# Liquid_Boost.net
KiCad netlist of a schematic drawn in Altium Designer
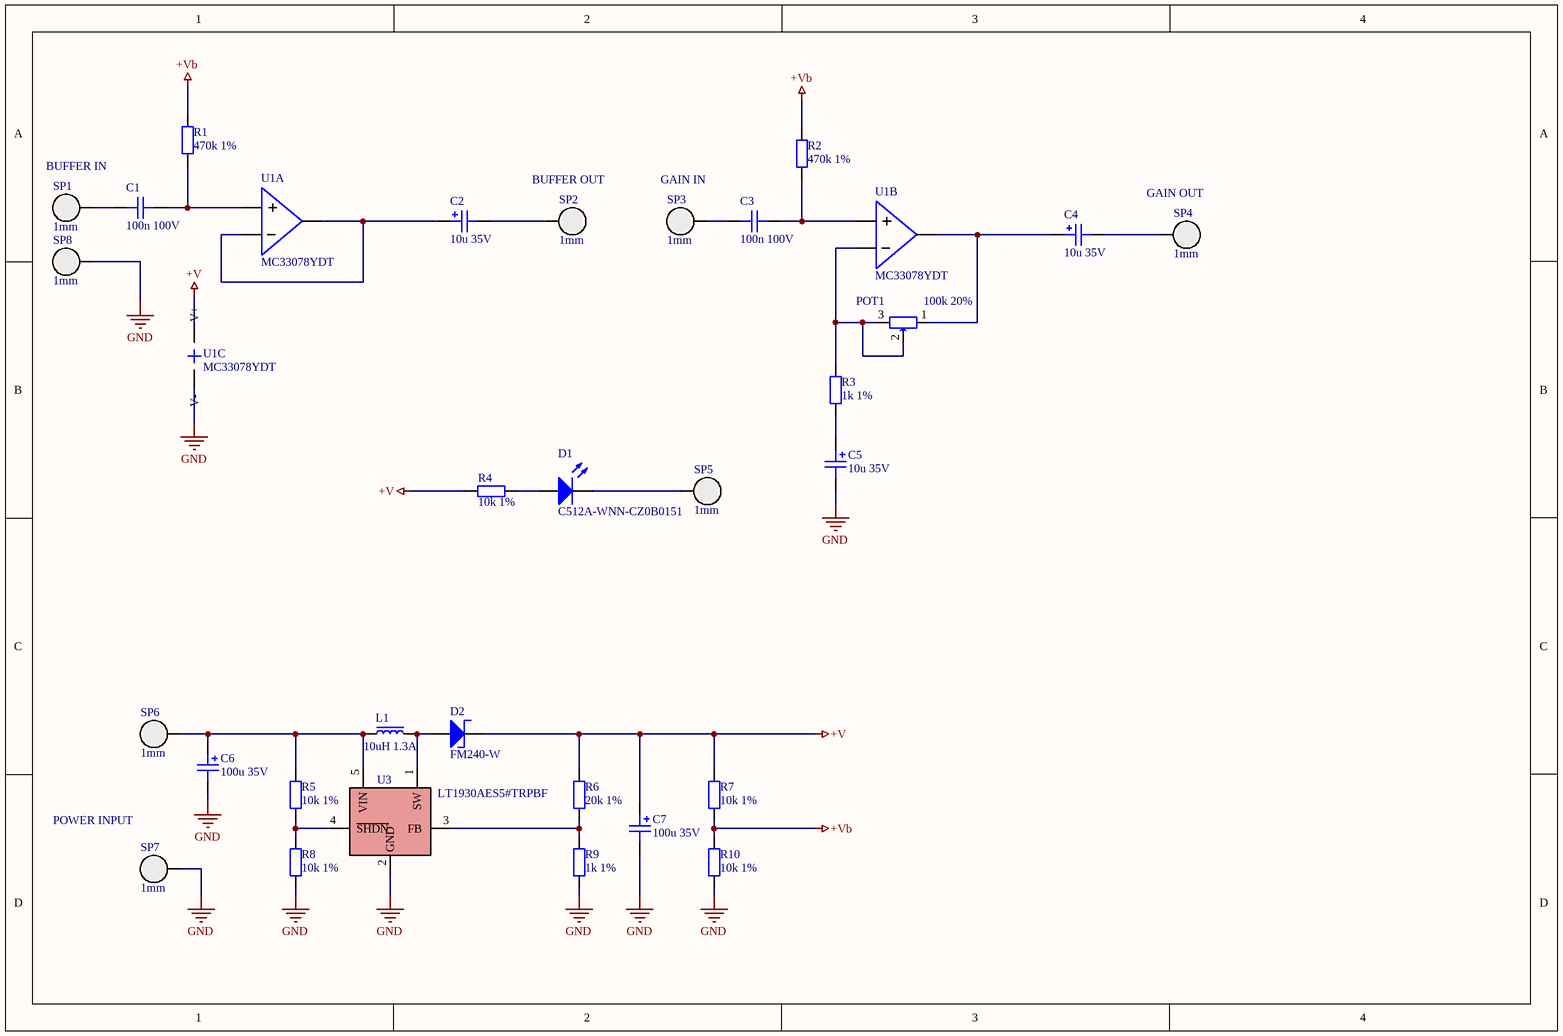
[diagram p0: Liquid Boost.SchDoc]

(export (version "E")
  (design (tool "Eeschema 10.0.6"))
  (components
    (comp (ref "C1")
      (value "100n 100V")
      (footprint "Liquid Boost:R82EC3100AA70K")
      (description "Film Capacitors 100V 0.1uF 10% LS=5mm AEC-Q200")
      (fields (field (name "MANUFACTURER PART NUMBER") "R82EC3100AA70K"))
      (libsource (lib "Liquid Boost") (part "Capacitor 100n 10% 100V R82EC3100AA70K"))
    )
    (comp (ref "C2")
      (value "10u 35V")
      (footprint "Liquid Boost:860010573007")
      (description "Aluminum Electrolytic Capacitors - Radial Leaded 10uF 35V 20% Audio SILMIC II")
      (fields (field (name "MANUFACTURER PART NUMBER") "RFS-35V100ME3#5"))
      (libsource (lib "Liquid Boost") (part "Capacitor 10u 35V 20% 5mm THT RFS-35V100ME3#5"))
    )
    (comp (ref "C3")
      (value "100n 100V")
      (footprint "Liquid Boost:R82EC3100AA70K")
      (description "Film Capacitors 100V 0.1uF 10% LS=5mm AEC-Q200")
      (fields (field (name "MANUFACTURER PART NUMBER") "R82EC3100AA70K"))
      (libsource (lib "Liquid Boost") (part "Capacitor 100n 10% 100V R82EC3100AA70K"))
    )
    (comp (ref "C4")
      (value "10u 35V")
      (footprint "Liquid Boost:860010573007")
      (description "Aluminum Electrolytic Capacitors - Radial Leaded 10uF 35V 20% Audio SILMIC II")
      (fields (field (name "MANUFACTURER PART NUMBER") "RFS-35V100ME3#5"))
      (libsource (lib "Liquid Boost") (part "Capacitor 10u 35V 20% 5mm THT RFS-35V100ME3#5"))
    )
    (comp (ref "C5")
      (value "10u 35V")
      (footprint "Liquid Boost:860010573007")
      (description "Aluminum Electrolytic Capacitors - Radial Leaded 10uF 35V 20% Audio SILMIC II")
      (fields (field (name "MANUFACTURER PART NUMBER") "RFS-35V100ME3#5"))
      (libsource (lib "Liquid Boost") (part "Capacitor 10u 35V 20% 5mm THT RFS-35V100ME3#5"))
    )
    (comp (ref "C6")
      (value "100u 35V")
      (footprint "Liquid Boost:860010573007")
      (description "Aluminum Electrolytic Capacitors - Radial Leaded WCAP-ATG8 100uF 35V 20% Radial")
      (fields (field (name "MANUFACTURER PART NUMBER") "860010573007"))
      (libsource (lib "Liquid Boost") (part "Capacitor 100u 35V 20% 6.3mm THT 860010573007"))
    )
    (comp (ref "C7")
      (value "100u 35V")
      (footprint "Liquid Boost:860010573007")
      (description "Aluminum Electrolytic Capacitors - Radial Leaded WCAP-ATG8 100uF 35V 20% Radial")
      (fields (field (name "MANUFACTURER PART NUMBER") "860010573007"))
      (libsource (lib "Liquid Boost") (part "Capacitor 100u 35V 20% 6.3mm THT 860010573007"))
    )
    (comp (ref "D1")
      (value "C512A-WNN-CZ0B0151")
      (footprint "Liquid Boost:C512A-WNN-CZ0B0151")
      (description "Standard LEDs - Through Hole Cool White 4600K 8200-23500mcd")
      (libsource (lib "Liquid Boost") (part "Diode LED 5mm White THT C512A-WNN-CZ0B0151"))
    )
    (comp (ref "D2")
      (value "FM240-W")
      (footprint "Liquid Boost:FM240-W")
      (description "Schottky Diodes & Rectifiers 2A 40V Schottky")
      (libsource (lib "Liquid Boost") (part "Diode Schottky 2A 40V FM240-W"))
    )
    (comp (ref "L1")
      (value "10uH 1.3A")
      (footprint "Liquid Boost:VLS252012HBX-100M-1")
      (description "Fixed Inductors 10uH 1.3A 540mOhms Power Circuits")
      (fields (field (name "MANUFACTURER PART NUMBER") "VLS252012HBX-100M-1"))
      (libsource (lib "Liquid Boost") (part "Inductor 10uH 1.3A 540mOhms VLS252012HBX-100M-1"))
    )
    (comp (ref "POT1")
      (value "100k 20%")
      (footprint "Liquid Boost:PTV09A")
      (description "Potentiometers 100K 20% 9MM CARBON POT")
      (fields (field (name "MANUFACTURER PART NUMBER") "PTV09A-4015F-B104"))
      (libsource (lib "Liquid Boost") (part "Potentiometer 100k 20% PTV09A-4015F-B104"))
    )
    (comp (ref "R1")
      (value "470k 1%")
      (footprint "Liquid Boost:Resistor 0603")
      (description "Thin Film Resistors - SMD 1/10W 470K ohm 1% 50ppm")
      (fields (field (name "MANUFACTURER PART NUMBER") "RT0603FRE07470KL"))
      (libsource (lib "Liquid Boost") (part "Resistor 470k 1% RT0603FRE07470KL"))
    )
    (comp (ref "R2")
      (value "470k 1%")
      (footprint "Liquid Boost:Resistor 0603")
      (description "Thin Film Resistors - SMD 1/10W 470K ohm 1% 50ppm")
      (fields (field (name "MANUFACTURER PART NUMBER") "RT0603FRE07470KL"))
      (libsource (lib "Liquid Boost") (part "Resistor 470k 1% RT0603FRE07470KL"))
    )
    (comp (ref "R3")
      (value "1k 1%")
      (footprint "Liquid Boost:Resistor 0603")
      (description "Thin Film Resistors - SMD 1K ohm 1% 1/10W")
      (fields (field (name "MANUFACTURER PART NUMBER") "RT0603FRE071KL"))
      (libsource (lib "Liquid Boost") (part "Resistor 1k 1% RT0603FRE071KL"))
    )
    (comp (ref "R4")
      (value "10k 1%")
      (footprint "Liquid Boost:Resistor 0603")
      (description "Thin Film Resistors - SMD 1/10W 10K ohm 1% 50ppm")
      (fields (field (name "MANUFACTURER PART NUMBER") "RT0603FRE0710KL"))
      (libsource (lib "") (part "Resistor 10k 1% RT0603FRE0710KL_1"))
    )
    (comp (ref "R5")
      (value "10k 1%")
      (footprint "Liquid Boost:Resistor 0603")
      (description "Thin Film Resistors - SMD 1/10W 10K ohm 1% 50ppm")
      (fields (field (name "MANUFACTURER PART NUMBER") "RT0603FRE0710KL"))
      (libsource (lib "Liquid Boost") (part "Resistor 10k 1% RT0603FRE0710KL"))
    )
    (comp (ref "R6")
      (value "20k 1%")
      (footprint "Liquid Boost:Resistor 0603")
      (description "Thin Film Resistors - SMD 1/10W 20K ohm 1% 50ppm")
      (fields (field (name "MANUFACTURER PART NUMBER") "RT0603FRE0720KL"))
      (libsource (lib "Liquid Boost") (part "Resistor 20k 1% RT0603FRE0720KL"))
    )
    (comp (ref "R7")
      (value "10k 1%")
      (footprint "Liquid Boost:Resistor 0603")
      (description "Thin Film Resistors - SMD 1/10W 10K ohm 1% 50ppm")
      (fields (field (name "MANUFACTURER PART NUMBER") "RT0603FRE0710KL"))
      (libsource (lib "Liquid Boost") (part "Resistor 10k 1% RT0603FRE0710KL"))
    )
    (comp (ref "R8")
      (value "10k 1%")
      (footprint "Liquid Boost:Resistor 0603")
      (description "Thin Film Resistors - SMD 1/10W 10K ohm 1% 50ppm")
      (fields (field (name "MANUFACTURER PART NUMBER") "RT0603FRE0710KL"))
      (libsource (lib "Liquid Boost") (part "Resistor 10k 1% RT0603FRE0710KL"))
    )
    (comp (ref "R9")
      (value "1k 1%")
      (footprint "Liquid Boost:Resistor 0603")
      (description "Thin Film Resistors - SMD 1K ohm 1% 1/10W")
      (fields (field (name "MANUFACTURER PART NUMBER") "RT0603FRE071KL"))
      (libsource (lib "Liquid Boost") (part "Resistor 1k 1% RT0603FRE071KL"))
    )
    (comp (ref "R10")
      (value "10k 1%")
      (footprint "Liquid Boost:Resistor 0603")
      (description "Thin Film Resistors - SMD 1/10W 10K ohm 1% 50ppm")
      (fields (field (name "MANUFACTURER PART NUMBER") "RT0603FRE0710KL"))
      (libsource (lib "Liquid Boost") (part "Resistor 10k 1% RT0603FRE0710KL"))
    )
    (comp (ref "SP1")
      (value "1mm")
      (footprint "Liquid Boost:SOLDER PAD 1mm")
      (libsource (lib "Liquid Boost") (part "Solder Pad 1mm"))
    )
    (comp (ref "SP2")
      (value "1mm")
      (footprint "Liquid Boost:SOLDER PAD 1mm")
      (libsource (lib "Liquid Boost") (part "Solder Pad 1mm"))
    )
    (comp (ref "SP3")
      (value "1mm")
      (footprint "Liquid Boost:SOLDER PAD 1mm")
      (libsource (lib "Liquid Boost") (part "Solder Pad 1mm"))
    )
    (comp (ref "SP4")
      (value "1mm")
      (footprint "Liquid Boost:SOLDER PAD 1mm")
      (libsource (lib "Liquid Boost") (part "Solder Pad 1mm"))
    )
    (comp (ref "SP5")
      (value "1mm")
      (footprint "Liquid Boost:SOLDER PAD 1mm")
      (libsource (lib "Liquid Boost") (part "Solder Pad 1mm"))
    )
    (comp (ref "SP6")
      (value "1mm")
      (footprint "Liquid Boost:SOLDER PAD 1mm")
      (libsource (lib "Liquid Boost") (part "Solder Pad 1mm"))
    )
    (comp (ref "SP7")
      (value "1mm")
      (footprint "Liquid Boost:SOLDER PAD 1mm")
      (libsource (lib "Liquid Boost") (part "Solder Pad 1mm"))
    )
    (comp (ref "SP8")
      (value "1mm")
      (footprint "Liquid Boost:SOLDER PAD 1mm")
      (libsource (lib "Liquid Boost") (part "Solder Pad 1mm"))
    )
    (comp (ref "U1")
      (value "MC33078YDT")
      (footprint "Liquid Boost:MC33078YDT")
      (description "Operational Amplifiers - Op Amps CONDITIONING & INTERFACES")
      (libsource (lib "Liquid Boost") (part "IC OP-AMP MC33078YDT SOP-8"))
    )
    (comp (ref "U3")
      (value "LT1930AES5#TRPBF")
      (footprint "Liquid Boost:LT1930AES5#TRPBF")
      (description "Switching Voltage Regulators 2.2MHz Boost Conv. in 5-lead SOT-23")
      (libsource (lib "Liquid Boost") (part "IC  Boost Converter LT1930AES5#TRPBF_1"))
    )
  )
  (nets
    (net (code "1") (name "+V") (class "Default")
      (node (ref "C7") (pin "1") (pinfunction "1_1") (pintype "passive"))
      (node (ref "D2") (pin "2") (pinfunction "2_2") (pintype "passive"))
      (node (ref "R4") (pin "2") (pinfunction "2_2") (pintype "passive"))
      (node (ref "R6") (pin "2") (pinfunction "2_2") (pintype "passive"))
      (node (ref "R7") (pin "2") (pinfunction "2_2") (pintype "passive"))
      (node (ref "U1") (pin "8") (pinfunction "V+_8") (pintype "passive"))
    )
    (net (code "2") (name "+Vb") (class "Default")
      (node (ref "R1") (pin "2") (pinfunction "2_2") (pintype "passive"))
      (node (ref "R10") (pin "2") (pinfunction "2_2") (pintype "passive"))
      (node (ref "R2") (pin "2") (pinfunction "2_2") (pintype "passive"))
      (node (ref "R7") (pin "1") (pinfunction "1_1") (pintype "passive"))
    )
    (net (code "3") (name "GND") (class "Default")
      (node (ref "C5") (pin "2") (pinfunction "2_2") (pintype "passive"))
      (node (ref "C6") (pin "2") (pinfunction "2_2") (pintype "passive"))
      (node (ref "C7") (pin "2") (pinfunction "2_2") (pintype "passive"))
      (node (ref "R10") (pin "1") (pinfunction "1_1") (pintype "passive"))
      (node (ref "R8") (pin "1") (pinfunction "1_1") (pintype "passive"))
      (node (ref "R9") (pin "1") (pinfunction "1_1") (pintype "passive"))
      (node (ref "SP7") (pin "1") (pinfunction "1_1") (pintype "passive"))
      (node (ref "SP8") (pin "1") (pinfunction "1_1") (pintype "passive"))
      (node (ref "U1") (pin "4") (pinfunction "V-_4") (pintype "passive"))
      (node (ref "U3") (pin "2") (pinfunction "GND_2") (pintype "passive"))
    )
    (net (code "4") (name "Net-(C1-Pad1)") (class "Default")
      (node (ref "C1") (pin "1") (pinfunction "1_1") (pintype "passive"))
      (node (ref "SP1") (pin "1") (pinfunction "1_1") (pintype "passive"))
    )
    (net (code "5") (name "Net-(C2-Pad2)") (class "Default")
      (node (ref "C2") (pin "2") (pinfunction "2_2") (pintype "passive"))
      (node (ref "SP2") (pin "1") (pinfunction "1_1") (pintype "passive"))
    )
    (net (code "6") (name "Net-(C3-Pad1)") (class "Default")
      (node (ref "C3") (pin "1") (pinfunction "1_1") (pintype "passive"))
      (node (ref "SP3") (pin "1") (pinfunction "1_1") (pintype "passive"))
    )
    (net (code "7") (name "Net-(C4-Pad2)") (class "Default")
      (node (ref "C4") (pin "2") (pinfunction "2_2") (pintype "passive"))
      (node (ref "SP4") (pin "1") (pinfunction "1_1") (pintype "passive"))
    )
    (net (code "8") (name "Net-(C5-Pad1)") (class "Default")
      (node (ref "C5") (pin "1") (pinfunction "1_1") (pintype "passive"))
      (node (ref "R3") (pin "1") (pinfunction "1_1") (pintype "passive"))
    )
    (net (code "9") (name "Net-(D1-Pad1)") (class "Default")
      (node (ref "D1") (pin "1") (pinfunction "1_1") (pintype "passive"))
      (node (ref "R4") (pin "1") (pinfunction "1_1") (pintype "passive"))
    )
    (net (code "10") (name "Net-(D1-Pad2)") (class "Default")
      (node (ref "D1") (pin "2") (pinfunction "2_2") (pintype "passive"))
      (node (ref "SP5") (pin "1") (pinfunction "1_1") (pintype "passive"))
    )
    (net (code "11") (name "Net-(U1A-IN+)") (class "Default")
      (node (ref "C1") (pin "2") (pinfunction "2_2") (pintype "passive"))
      (node (ref "R1") (pin "1") (pinfunction "1_1") (pintype "passive"))
      (node (ref "U1") (pin "3") (pinfunction "IN+_3") (pintype "passive"))
    )
    (net (code "12") (name "Net-(U1A-IN-)") (class "Default")
      (node (ref "C2") (pin "1") (pinfunction "1_1") (pintype "passive"))
      (node (ref "U1") (pin "1") (pinfunction "OUT_1") (pintype "passive"))
      (node (ref "U1") (pin "2") (pinfunction "IN-_2") (pintype "passive"))
    )
    (net (code "13") (name "Net-(U1B-IN+)") (class "Default")
      (node (ref "C3") (pin "2") (pinfunction "2_2") (pintype "passive"))
      (node (ref "R2") (pin "1") (pinfunction "1_1") (pintype "passive"))
      (node (ref "U1") (pin "5") (pinfunction "IN+_5") (pintype "passive"))
    )
    (net (code "14") (name "Net-(U1B-IN-)") (class "Default")
      (node (ref "POT1") (pin "2") (pinfunction "2_2") (pintype "passive"))
      (node (ref "POT1") (pin "3") (pinfunction "3_3") (pintype "passive"))
      (node (ref "R3") (pin "2") (pinfunction "2_2") (pintype "passive"))
      (node (ref "U1") (pin "6") (pinfunction "IN-_6") (pintype "passive"))
    )
    (net (code "15") (name "Net-(U1B-OUT)") (class "Default")
      (node (ref "C4") (pin "1") (pinfunction "1_1") (pintype "passive"))
      (node (ref "POT1") (pin "1") (pinfunction "1_1") (pintype "passive"))
      (node (ref "U1") (pin "7") (pinfunction "OUT_7") (pintype "passive"))
    )
    (net (code "16") (name "Net-(U3-FB)") (class "Default")
      (node (ref "R6") (pin "1") (pinfunction "1_1") (pintype "passive"))
      (node (ref "R9") (pin "2") (pinfunction "2_2") (pintype "passive"))
      (node (ref "U3") (pin "3") (pinfunction "FB_3") (pintype "passive"))
    )
    (net (code "17") (name "Net-(U3-SW)") (class "Default")
      (node (ref "D2") (pin "1") (pinfunction "1_1") (pintype "passive"))
      (node (ref "L1") (pin "2") (pinfunction "2_2") (pintype "passive"))
      (node (ref "U3") (pin "1") (pinfunction "SW_1") (pintype "passive"))
    )
    (net (code "18") (name "Net-(U3-VIN)") (class "Default")
      (node (ref "C6") (pin "1") (pinfunction "1_1") (pintype "passive"))
      (node (ref "L1") (pin "1") (pinfunction "1_1") (pintype "passive"))
      (node (ref "R5") (pin "2") (pinfunction "2_2") (pintype "passive"))
      (node (ref "SP6") (pin "1") (pinfunction "1_1") (pintype "passive"))
      (node (ref "U3") (pin "5") (pinfunction "VIN_5") (pintype "passive"))
    )
    (net (code "19") (name "Net-(U3-~{SHDN})") (class "Default")
      (node (ref "R5") (pin "1") (pinfunction "1_1") (pintype "passive"))
      (node (ref "R8") (pin "2") (pinfunction "2_2") (pintype "passive"))
      (node (ref "U3") (pin "4") (pinfunction "~{SHDN}_4") (pintype "passive"))
    )
  )
)
